# 3_3V_to_0_9V.net
KiCad netlist of a schematic drawn in Altium Designer
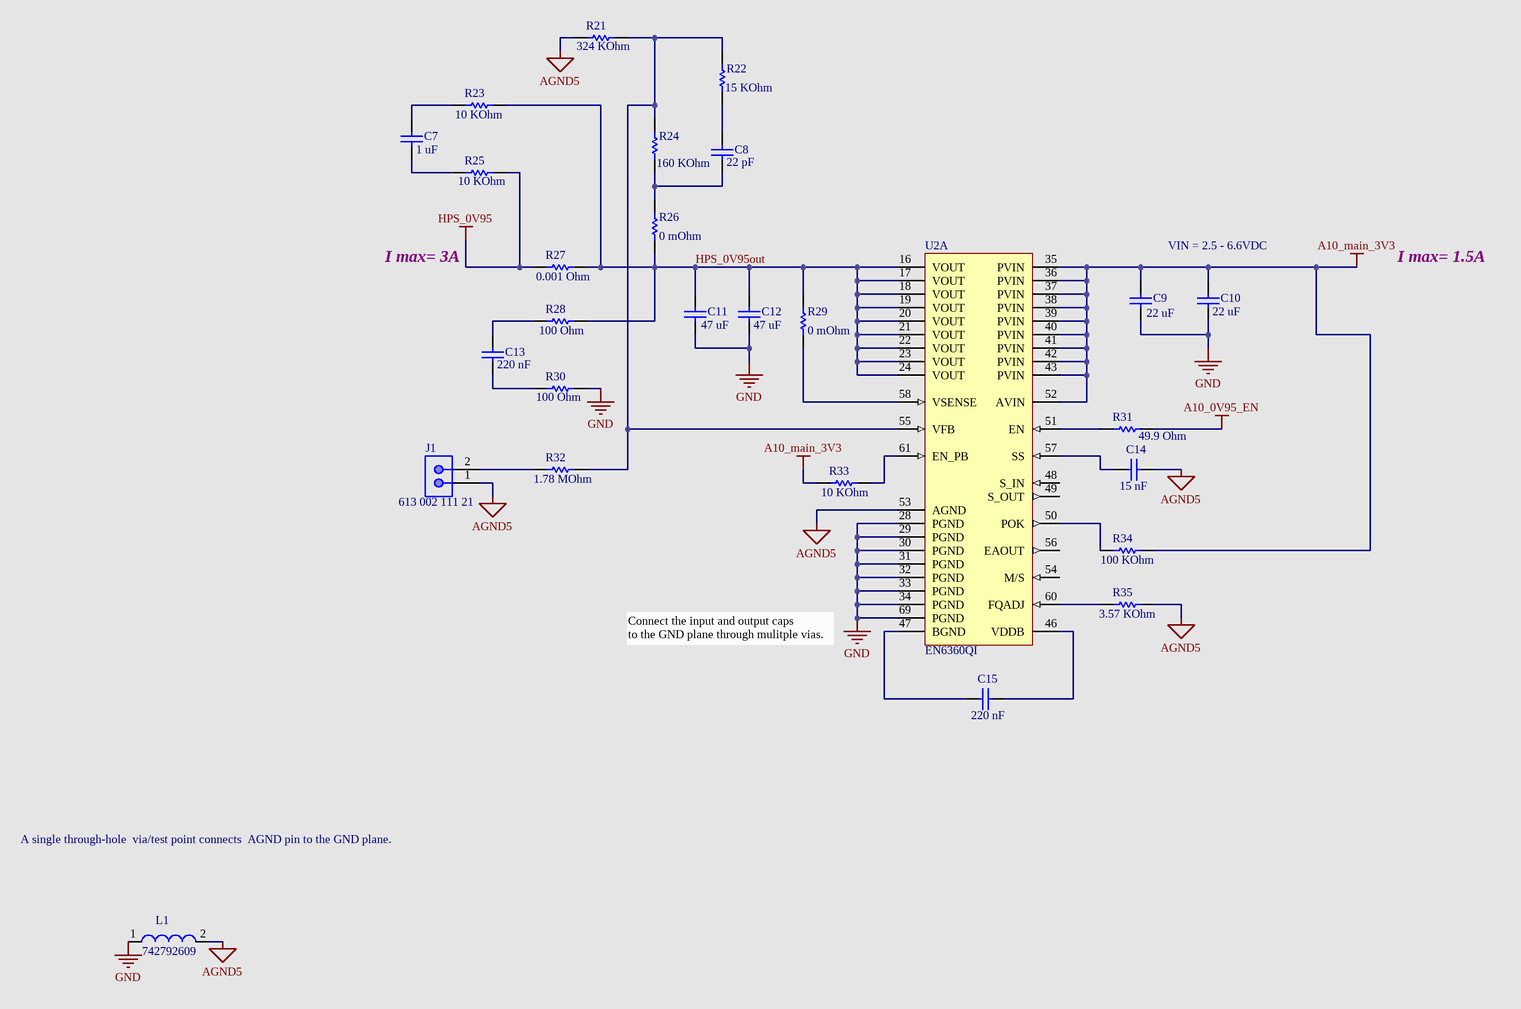
[diagram p0: 3.3V_to_0.9V.SchDoc]

(export (version "E")
  (design (tool "Eeschema 10.0.6"))
  (components
    (comp (ref "C7")
      (value "CGB2A1X5R1E105K033BC")
      (footprint "CAPC1005X33X10LL5")
      (description "Chip Capacitor, 1 uF, +/- 10%, 25 V, -55 to 85 degC, 0402 (1005 Metric), RoHS, Tape and Reel")
      (fields (field (name "TOLERANCE") "10%") (field (name "CAPACITANCE") "1 uF"))
      (libsource (lib "") (part "CAP-NP-2_1"))
    )
    (comp (ref "C8")
      (value "C1005C0G1H220J050BA")
      (footprint "CAPC1005X55X10LL05")
      (description "Chip Capacitor, 22 pF, +/- 5%, 50 V, -55 to 125 degC, 0402 (1005 Metric), RoHS, Tape and Reel")
      (fields (field (name "TOLERANCE") "5%") (field (name "CAPACITANCE") "22 pF"))
      (libsource (lib "Altium Content Vault") (part "CAP-NP-2"))
    )
    (comp (ref "C9")
      (value "GRM31CR61E226KE15L")
      (footprint "CAPC3216X180X55ML20T25")
      (description "Chip Capacitor, 22 uF, +/- 10%, 25 V, -55 to 85 degC, 1206 (3216 Metric), RoHS, Tape and Reel")
      (fields (field (name "TOLERANCE") "10%") (field (name "CAPACITANCE") "22 uF"))
      (libsource (lib "Altium Content Vault") (part "CAP-NP-2"))
    )
    (comp (ref "C10")
      (value "GRM31CR61E226KE15L")
      (footprint "CAPC3216X180X55ML20T25")
      (description "Chip Capacitor, 22 uF, +/- 10%, 25 V, -55 to 85 degC, 1206 (3216 Metric), RoHS, Tape and Reel")
      (fields (field (name "TOLERANCE") "10%") (field (name "CAPACITANCE") "22 uF"))
      (libsource (lib "Altium Content Vault") (part "CAP-NP-2"))
    )
    (comp (ref "C11")
      (value "C3216X5R1A476M160AB")
      (footprint "CAPC3216X180X20ML20")
      (description "Chip Capacitor, 47 uF, +/- 20%, 10 V, -55 to 85 degC, 1206 (3216 Metric), RoHS, Tape and Reel")
      (fields (field (name "TOLERANCE") "20%") (field (name "CAPACITANCE") "47 uF"))
      (libsource (lib "") (part "CAP-NP-2_1"))
    )
    (comp (ref "C12")
      (value "C3216X5R1A476M160AB")
      (footprint "CAPC3216X180X20ML20")
      (description "Chip Capacitor, 47 uF, +/- 20%, 10 V, -55 to 85 degC, 1206 (3216 Metric), RoHS, Tape and Reel")
      (fields (field (name "TOLERANCE") "20%") (field (name "CAPACITANCE") "47 uF"))
      (libsource (lib "") (part "CAP-NP-2_1"))
    )
    (comp (ref "C13")
      (value "GRM155R61A224KE19D")
      (footprint "CAPC1005X55X25NL05T10")
      (description "Chip Capacitor, 220 nF, +/- 10%, 10 V, -55 to 85 degC, 0402 (1005 Metric), RoHS, Tape and Reel")
      (fields
        (field (name "TOLERANCE") "10%")
        (field (name "CAPACITANCE") "220 nF")
        (field (name "MANUFACTURER") "Basic Passives")
      )
      (libsource (lib "Altium Content Vault") (part "CAP-NP-2"))
    )
    (comp (ref "C14")
      (value "VJ0402Y153JXQPW1BC")
      (footprint "CAPC1005X55X23ML05T8")
      (description "Chip Capacitor, 15 nF, +/- 5%, 10 V, -55 to 125 degC, 0402 (1005 Metric), RoHS, Tape and Reel")
      (fields (field (name "CAPACITANCE") "15 nF") (field (name "TOLERANCE") "5%"))
      (libsource (lib "Altium Content Vault") (part "CAP-NP-2"))
    )
    (comp (ref "C15")
      (value "GRM155R61A224KE19D")
      (footprint "CAPC1005X55X25NL05T10")
      (description "Chip Capacitor, 220 nF, +/- 10%, 10 V, -55 to 85 degC, 0402 (1005 Metric), RoHS, Tape and Reel")
      (fields
        (field (name "TOLERANCE") "10%")
        (field (name "CAPACITANCE") "220 nF")
        (field (name "MANUFACTURER") "Basic Passives")
      )
      (libsource (lib "Altium Content Vault") (part "CAP-NP-2"))
    )
    (comp (ref "J1")
      (value "613 002 111 21")
      (footprint "WE-61300211121_V")
      (fields (field (name "MANUFACTURER") "Wuerth Elektronik"))
      (libsource (lib "Altium Content Vault") (part "CMP-1712-00002-1"))
    )
    (comp (ref "L1")
      (value "742792609")
      (footprint "SMD-0603")
      (description "SMD EMI Suppression Ferrite Bead WE-CBF, Z = 30 Ohm")
      (libsource (lib "Altium Content Vault") (part "CMP-0220-00193-1"))
    )
    (comp (ref "R21")
      (value "ERJ-2RKF3243X")
      (footprint "RESC1005X40X25ML05T05")
      (description "Chip Resistor, 324 KOhm, +/- 1%, 100 mW, -55 to 155 degC, 0402 (1005 Metric), RoHS, Tape and Reel")
      (fields
        (field (name "MANUFACTURER") "Basic Passives")
        (field (name "TOLERANCE") "1%")
        (field (name "RESISTANCE") "324 KOhm")
      )
      (libsource (lib "Altium Content Vault") (part "RES-2"))
    )
    (comp (ref "R22")
      (value "ERJ-2RKF1502X")
      (footprint "RESC1005X40X25ML05T05")
      (description "Chip Resistor, 15 KOhm, +/- 1%, 100 mW, -55 to 155 degC, 0402 (1005 Metric), RoHS, Tape and Reel")
      (fields
        (field (name "RESISTANCE") "15 KOhm")
        (field (name "TOLERANCE") "1%")
        (field (name "MANUFACTURER") "Basic Passives")
      )
      (libsource (lib "Altium Content Vault") (part "RES-2"))
    )
    (comp (ref "R23")
      (value "ERJ-2RKF1002X")
      (footprint "RESC1005X40X25NL05T05")
      (description "Chip Resistor, 10 KOhm, +/- 1%, 100 mW, -55 to 155 degC, 0402 (1005 Metric), RoHS, Tape and Reel")
      (fields
        (field (name "TOLERANCE") "1%")
        (field (name "RESISTANCE") "10 KOhm")
        (field (name "MANUFACTURER") "Basic Passives")
      )
      (libsource (lib "Altium Content Vault") (part "RES-2"))
    )
    (comp (ref "R24")
      (value "CRCW0402160KFKED")
      (footprint "RESC1005X40X25ML05T05")
      (description "Chip Resistor, 160 KOhm, +/- 1%, 63 mW, -55 to 155 degC, 0402 (1005 Metric), RoHS, Tape and Reel")
      (fields
        (field (name "TOLERANCE") "1%")
        (field (name "RESISTANCE") "160 KOhm")
        (field (name "MANUFACTURER") "Basic Passives")
      )
      (libsource (lib "Altium Content Vault") (part "RES-2"))
    )
    (comp (ref "R25")
      (value "ERJ-2RKF1002X")
      (footprint "RESC1005X40X25NL05T05")
      (description "Chip Resistor, 10 KOhm, +/- 1%, 100 mW, -55 to 155 degC, 0402 (1005 Metric), RoHS, Tape and Reel")
      (fields
        (field (name "TOLERANCE") "1%")
        (field (name "RESISTANCE") "10 KOhm")
        (field (name "MANUFACTURER") "Basic Passives")
      )
      (libsource (lib "Altium Content Vault") (part "RES-2"))
    )
    (comp (ref "R26")
      (value "ERJ-2GE0R00X")
      (footprint "RESC1005X40X25ML05T05")
      (description "Chip Resistor, 0 mOhm, +/- 5%, 100 mW, -55 to 155 degC, 0402 (1005 Metric), RoHS, Tape and Reel")
      (fields
        (field (name "TOLERANCE") "5%")
        (field (name "RESISTANCE") "0 mOhm")
        (field (name "MANUFACTURER") "Basic Passives")
      )
      (libsource (lib "Altium Content Vault") (part "RES-2"))
    )
    (comp (ref "R27")
      (value "WSLP12061L000FEA")
      (footprint "RESC3216X89X104LL25T25")
      (description "Chip Resistor, 0.001 Ohm, +/- 1%, 1 W, -65 to 170 degC, 1206 (3216 Metric), RoHS, Tape and Reel")
      (fields (field (name "TOLERANCE") "1%") (field (name "RESISTANCE") "0.001 Ohm"))
      (libsource (lib "Altium Content Vault") (part "RES-2"))
    )
    (comp (ref "R28")
      (value "ERJ-2RKF1000X")
      (footprint "RESC1005X40X25LL05T05")
      (description "Chip Resistor, 100 Ohm, +/- 1%, 100 mW, -55 to 155 degC, 0402 (1005 Metric), RoHS, Tape and Reel")
      (fields
        (field (name "TOLERANCE") "1%")
        (field (name "RESISTANCE") "100 Ohm")
        (field (name "MANUFACTURER") "Basic Passives")
      )
      (libsource (lib "Altium Content Vault") (part "RES-2"))
    )
    (comp (ref "R29")
      (value "ERJ-2GE0R00X")
      (footprint "RESC1005X40X25ML05T05")
      (description "Chip Resistor, 0 mOhm, +/- 5%, 100 mW, -55 to 155 degC, 0402 (1005 Metric), RoHS, Tape and Reel")
      (fields
        (field (name "TOLERANCE") "5%")
        (field (name "RESISTANCE") "0 mOhm")
        (field (name "MANUFACTURER") "Basic Passives")
      )
      (libsource (lib "Altium Content Vault") (part "RES-2"))
    )
    (comp (ref "R30")
      (value "ERJ-2RKF1000X")
      (footprint "RESC1005X40X25LL05T05")
      (description "Chip Resistor, 100 Ohm, +/- 1%, 100 mW, -55 to 155 degC, 0402 (1005 Metric), RoHS, Tape and Reel")
      (fields
        (field (name "TOLERANCE") "1%")
        (field (name "RESISTANCE") "100 Ohm")
        (field (name "MANUFACTURER") "Basic Passives")
      )
      (libsource (lib "Altium Content Vault") (part "RES-2"))
    )
    (comp (ref "R31")
      (value "NRC04F49R9TRF")
      (footprint "RESC1005X35X25NL8T10")
      (description "Chip Resistor, 49.9 Ohm, +/- 1%, 0.06 W, -55 to 155 degC, 0402 (1005 Metric), RoHS, Tape and Reel")
      (fields (field (name "TOLERANCE") "1%") (field (name "RESISTANCE") "49.9 Ohm"))
      (libsource (lib "Altium Content Vault") (part "RES-2"))
    )
    (comp (ref "R32")
      (value "CRCW04021M78FKED")
      (footprint "RESC1005X40X25ML05T05")
      (description "Chip Resistor, 1.78 MOhm, +/- 1%, 63 mW, -55 to 155 degC, 0402 (1005 Metric), RoHS, Tape and Reel")
      (fields
        (field (name "TOLERANCE") "1%")
        (field (name "RESISTANCE") "1.78 MOhm")
        (field (name "MANUFACTURER") "Basic Passives")
      )
      (libsource (lib "Altium Content Vault") (part "RES-2"))
    )
    (comp (ref "R33")
      (value "ERJ-2RKF1002X")
      (footprint "RESC1005X40X25NL05T05")
      (description "Chip Resistor, 10 KOhm, +/- 1%, 100 mW, -55 to 155 degC, 0402 (1005 Metric), RoHS, Tape and Reel")
      (fields
        (field (name "TOLERANCE") "1%")
        (field (name "RESISTANCE") "10 KOhm")
        (field (name "MANUFACTURER") "Basic Passives")
      )
      (libsource (lib "Altium Content Vault") (part "RES-2"))
    )
    (comp (ref "R34")
      (value "ERJ-2RKF1003X")
      (footprint "RESC1005X40X25LL05T05")
      (description "Chip Resistor, 100 KOhm, +/- 1%, 100 mW, -55 to 155 degC, 0402 (1005 Metric), RoHS, Tape and Reel")
      (fields
        (field (name "RESISTANCE") "100 KOhm")
        (field (name "TOLERANCE") "1%")
        (field (name "MANUFACTURER") "Basic Passives")
      )
      (libsource (lib "Altium Content Vault") (part "RES-2"))
    )
    (comp (ref "R35")
      (value "CRCW04023K57FKED")
      (footprint "RESC1005X40X25NL05T05")
      (description "Chip Resistor, 3.57 KOhm, +/- 1%, 63 mW, -55 to 155 degC, 0402 (1005 Metric), RoHS, Tape and Reel")
      (fields (field (name "RESISTANCE") "3.57 KOhm") (field (name "TOLERANCE") "1%"))
      (libsource (lib "Altium Content Vault") (part "RES"))
    )
    (comp (ref "U2")
      (value "EN6360QI")
      (footprint "ALTR-QFN-68_A-305_V")
      (libsource (lib "Altium Content Vault") (part "ALTR-EN6360QI-QFN68"))
    )
  )
  (nets
    (net (code "1") (name "/HPS_0V95out") (class "Default")
      (node (ref "C11") (pin "2") (pinfunction "2_2") (pintype "passive"))
      (node (ref "C12") (pin "2") (pinfunction "2_2") (pintype "passive"))
      (node (ref "R23") (pin "2") (pinfunction "2_2") (pintype "passive"))
      (node (ref "R26") (pin "1") (pinfunction "1_1") (pintype "passive"))
      (node (ref "R27") (pin "2") (pinfunction "2_2") (pintype "passive"))
      (node (ref "R28") (pin "1") (pinfunction "1_1") (pintype "passive"))
      (node (ref "R29") (pin "2") (pinfunction "2_2") (pintype "passive"))
      (node (ref "U2") (pin "16") (pinfunction "VOUT_16") (pintype "power_in"))
      (node (ref "U2") (pin "17") (pinfunction "VOUT_17") (pintype "power_in"))
      (node (ref "U2") (pin "18") (pinfunction "VOUT_18") (pintype "power_in"))
      (node (ref "U2") (pin "19") (pinfunction "VOUT_19") (pintype "power_in"))
      (node (ref "U2") (pin "20") (pinfunction "VOUT_20") (pintype "power_in"))
      (node (ref "U2") (pin "21") (pinfunction "VOUT_21") (pintype "power_in"))
      (node (ref "U2") (pin "22") (pinfunction "VOUT_22") (pintype "power_in"))
      (node (ref "U2") (pin "23") (pinfunction "VOUT_23") (pintype "power_in"))
      (node (ref "U2") (pin "24") (pinfunction "VOUT_24") (pintype "power_in"))
    )
    (net (code "2") (name "A10_0V95_EN") (class "Default")
      (node (ref "R31") (pin "2") (pinfunction "2_2") (pintype "passive"))
    )
    (net (code "3") (name "A10_main_3V3") (class "Default")
      (node (ref "C10") (pin "2") (pinfunction "2_2") (pintype "passive"))
      (node (ref "C9") (pin "2") (pinfunction "2_2") (pintype "passive"))
      (node (ref "R33") (pin "1") (pinfunction "1_1") (pintype "passive"))
      (node (ref "R34") (pin "2") (pinfunction "2_2") (pintype "passive"))
      (node (ref "U2") (pin "35") (pinfunction "PVIN_35") (pintype "power_in"))
      (node (ref "U2") (pin "36") (pinfunction "PVIN_36") (pintype "power_in"))
      (node (ref "U2") (pin "37") (pinfunction "PVIN_37") (pintype "power_in"))
      (node (ref "U2") (pin "38") (pinfunction "PVIN_38") (pintype "power_in"))
      (node (ref "U2") (pin "39") (pinfunction "PVIN_39") (pintype "power_in"))
      (node (ref "U2") (pin "40") (pinfunction "PVIN_40") (pintype "power_in"))
      (node (ref "U2") (pin "41") (pinfunction "PVIN_41") (pintype "power_in"))
      (node (ref "U2") (pin "42") (pinfunction "PVIN_42") (pintype "power_in"))
      (node (ref "U2") (pin "43") (pinfunction "PVIN_43") (pintype "power_in"))
      (node (ref "U2") (pin "52") (pinfunction "AVIN_52") (pintype "power_in"))
    )
    (net (code "4") (name "AGND5") (class "Default")
      (node (ref "C14") (pin "1") (pinfunction "1_1") (pintype "passive"))
      (node (ref "J1") (pin "1") (pinfunction "1_1") (pintype "passive"))
      (node (ref "L1") (pin "2") (pinfunction "2_2") (pintype "passive"))
      (node (ref "R21") (pin "1") (pinfunction "1_1") (pintype "passive"))
      (node (ref "R35") (pin "2") (pinfunction "2_2") (pintype "passive"))
      (node (ref "U2") (pin "53") (pinfunction "AGND_53") (pintype "power_in"))
    )
    (net (code "5") (name "GND") (class "Default")
      (node (ref "C10") (pin "1") (pinfunction "1_1") (pintype "passive"))
      (node (ref "C11") (pin "1") (pinfunction "1_1") (pintype "passive"))
      (node (ref "C12") (pin "1") (pinfunction "1_1") (pintype "passive"))
      (node (ref "C9") (pin "1") (pinfunction "1_1") (pintype "passive"))
      (node (ref "L1") (pin "1") (pinfunction "1_1") (pintype "passive"))
      (node (ref "R30") (pin "1") (pinfunction "1_1") (pintype "passive"))
      (node (ref "U2") (pin "28") (pinfunction "PGND_28") (pintype "power_in"))
      (node (ref "U2") (pin "29") (pinfunction "PGND_29") (pintype "power_in"))
      (node (ref "U2") (pin "30") (pinfunction "PGND_30") (pintype "power_in"))
      (node (ref "U2") (pin "31") (pinfunction "PGND_31") (pintype "power_in"))
      (node (ref "U2") (pin "32") (pinfunction "PGND_32") (pintype "power_in"))
      (node (ref "U2") (pin "33") (pinfunction "PGND_33") (pintype "power_in"))
      (node (ref "U2") (pin "34") (pinfunction "PGND_34") (pintype "power_in"))
      (node (ref "U2") (pin "69") (pinfunction "PGND_69") (pintype "power_in"))
    )
    (net (code "6") (name "HPS_0V95") (class "Default")
      (node (ref "R25") (pin "2") (pinfunction "2_2") (pintype "passive"))
      (node (ref "R27") (pin "1") (pinfunction "1_1") (pintype "passive"))
    )
    (net (code "7") (name "Net-(C7-Pad1)") (class "Default")
      (node (ref "C7") (pin "1") (pinfunction "1_1") (pintype "passive"))
      (node (ref "R25") (pin "1") (pinfunction "1_1") (pintype "passive"))
    )
    (net (code "8") (name "Net-(C7-Pad2)") (class "Default")
      (node (ref "C7") (pin "2") (pinfunction "2_2") (pintype "passive"))
      (node (ref "R23") (pin "1") (pinfunction "1_1") (pintype "passive"))
    )
    (net (code "9") (name "Net-(C8-Pad1)") (class "Default")
      (node (ref "C8") (pin "1") (pinfunction "1_1") (pintype "passive"))
      (node (ref "R24") (pin "1") (pinfunction "1_1") (pintype "passive"))
      (node (ref "R26") (pin "2") (pinfunction "2_2") (pintype "passive"))
    )
    (net (code "10") (name "Net-(C8-Pad2)") (class "Default")
      (node (ref "C8") (pin "2") (pinfunction "2_2") (pintype "passive"))
      (node (ref "R22") (pin "1") (pinfunction "1_1") (pintype "passive"))
    )
    (net (code "11") (name "Net-(C13-Pad1)") (class "Default")
      (node (ref "C13") (pin "1") (pinfunction "1_1") (pintype "passive"))
      (node (ref "R28") (pin "2") (pinfunction "2_2") (pintype "passive"))
    )
    (net (code "12") (name "Net-(C13-Pad2)") (class "Default")
      (node (ref "C13") (pin "2") (pinfunction "2_2") (pintype "passive"))
      (node (ref "R30") (pin "2") (pinfunction "2_2") (pintype "passive"))
    )
    (net (code "13") (name "Net-(J1-Pad2)") (class "Default")
      (node (ref "J1") (pin "2") (pinfunction "2_2") (pintype "passive"))
      (node (ref "R32") (pin "1") (pinfunction "1_1") (pintype "passive"))
    )
    (net (code "14") (name "Net-(U2A-BGND)") (class "Default")
      (node (ref "C15") (pin "1") (pinfunction "1_1") (pintype "passive"))
      (node (ref "U2") (pin "47") (pinfunction "BGND_47") (pintype "power_in"))
    )
    (net (code "15") (name "Net-(U2A-EN)") (class "Default")
      (node (ref "R31") (pin "1") (pinfunction "1_1") (pintype "passive"))
      (node (ref "U2") (pin "51") (pinfunction "EN_51") (pintype "input"))
    )
    (net (code "16") (name "Net-(U2A-EN_PB)") (class "Default")
      (node (ref "R33") (pin "2") (pinfunction "2_2") (pintype "passive"))
      (node (ref "U2") (pin "61") (pinfunction "EN_PB_61") (pintype "input"))
    )
    (net (code "17") (name "Net-(U2A-FQADJ)") (class "Default")
      (node (ref "R35") (pin "1") (pinfunction "1_1") (pintype "passive"))
      (node (ref "U2") (pin "60") (pinfunction "FQADJ_60") (pintype "input"))
    )
    (net (code "18") (name "Net-(U2A-POK)") (class "Default")
      (node (ref "R34") (pin "1") (pinfunction "1_1") (pintype "passive"))
      (node (ref "U2") (pin "50") (pinfunction "POK_50") (pintype "output"))
    )
    (net (code "19") (name "Net-(U2A-SS)") (class "Default")
      (node (ref "C14") (pin "2") (pinfunction "2_2") (pintype "passive"))
      (node (ref "U2") (pin "57") (pinfunction "SS_57") (pintype "input"))
    )
    (net (code "20") (name "Net-(U2A-VDDB)") (class "Default")
      (node (ref "C15") (pin "2") (pinfunction "2_2") (pintype "passive"))
      (node (ref "U2") (pin "46") (pinfunction "VDDB_46") (pintype "power_in"))
    )
    (net (code "21") (name "Net-(U2A-VFB)") (class "Default")
      (node (ref "R21") (pin "2") (pinfunction "2_2") (pintype "passive"))
      (node (ref "R22") (pin "2") (pinfunction "2_2") (pintype "passive"))
      (node (ref "R24") (pin "2") (pinfunction "2_2") (pintype "passive"))
      (node (ref "R32") (pin "2") (pinfunction "2_2") (pintype "passive"))
      (node (ref "U2") (pin "55") (pinfunction "VFB_55") (pintype "input"))
    )
    (net (code "22") (name "Net-(U2A-VSENSE)") (class "Default")
      (node (ref "R29") (pin "1") (pinfunction "1_1") (pintype "passive"))
      (node (ref "U2") (pin "58") (pinfunction "VSENSE_58") (pintype "input"))
    )
    (net (code "23") (name "unconnected-(U2A-EAOUT-Pad56)") (class "Default")
      (node (ref "U2") (pin "56") (pinfunction "EAOUT_56") (pintype "output"))
    )
    (net (code "24") (name "unconnected-(U2A-M{slash}S-Pad54)") (class "Default")
      (node (ref "U2") (pin "54") (pinfunction "M/S_54") (pintype "input"))
    )
    (net (code "25") (name "unconnected-(U2A-S_IN-Pad48)") (class "Default")
      (node (ref "U2") (pin "48") (pinfunction "S_IN_48") (pintype "input"))
    )
    (net (code "26") (name "unconnected-(U2A-S_OUT-Pad49)") (class "Default")
      (node (ref "U2") (pin "49") (pinfunction "S_OUT_49") (pintype "output"))
    )
  )
)
